# Qwiic_AHT20_Breakout.net
KiCad netlist of a schematic drawn in EAGLE
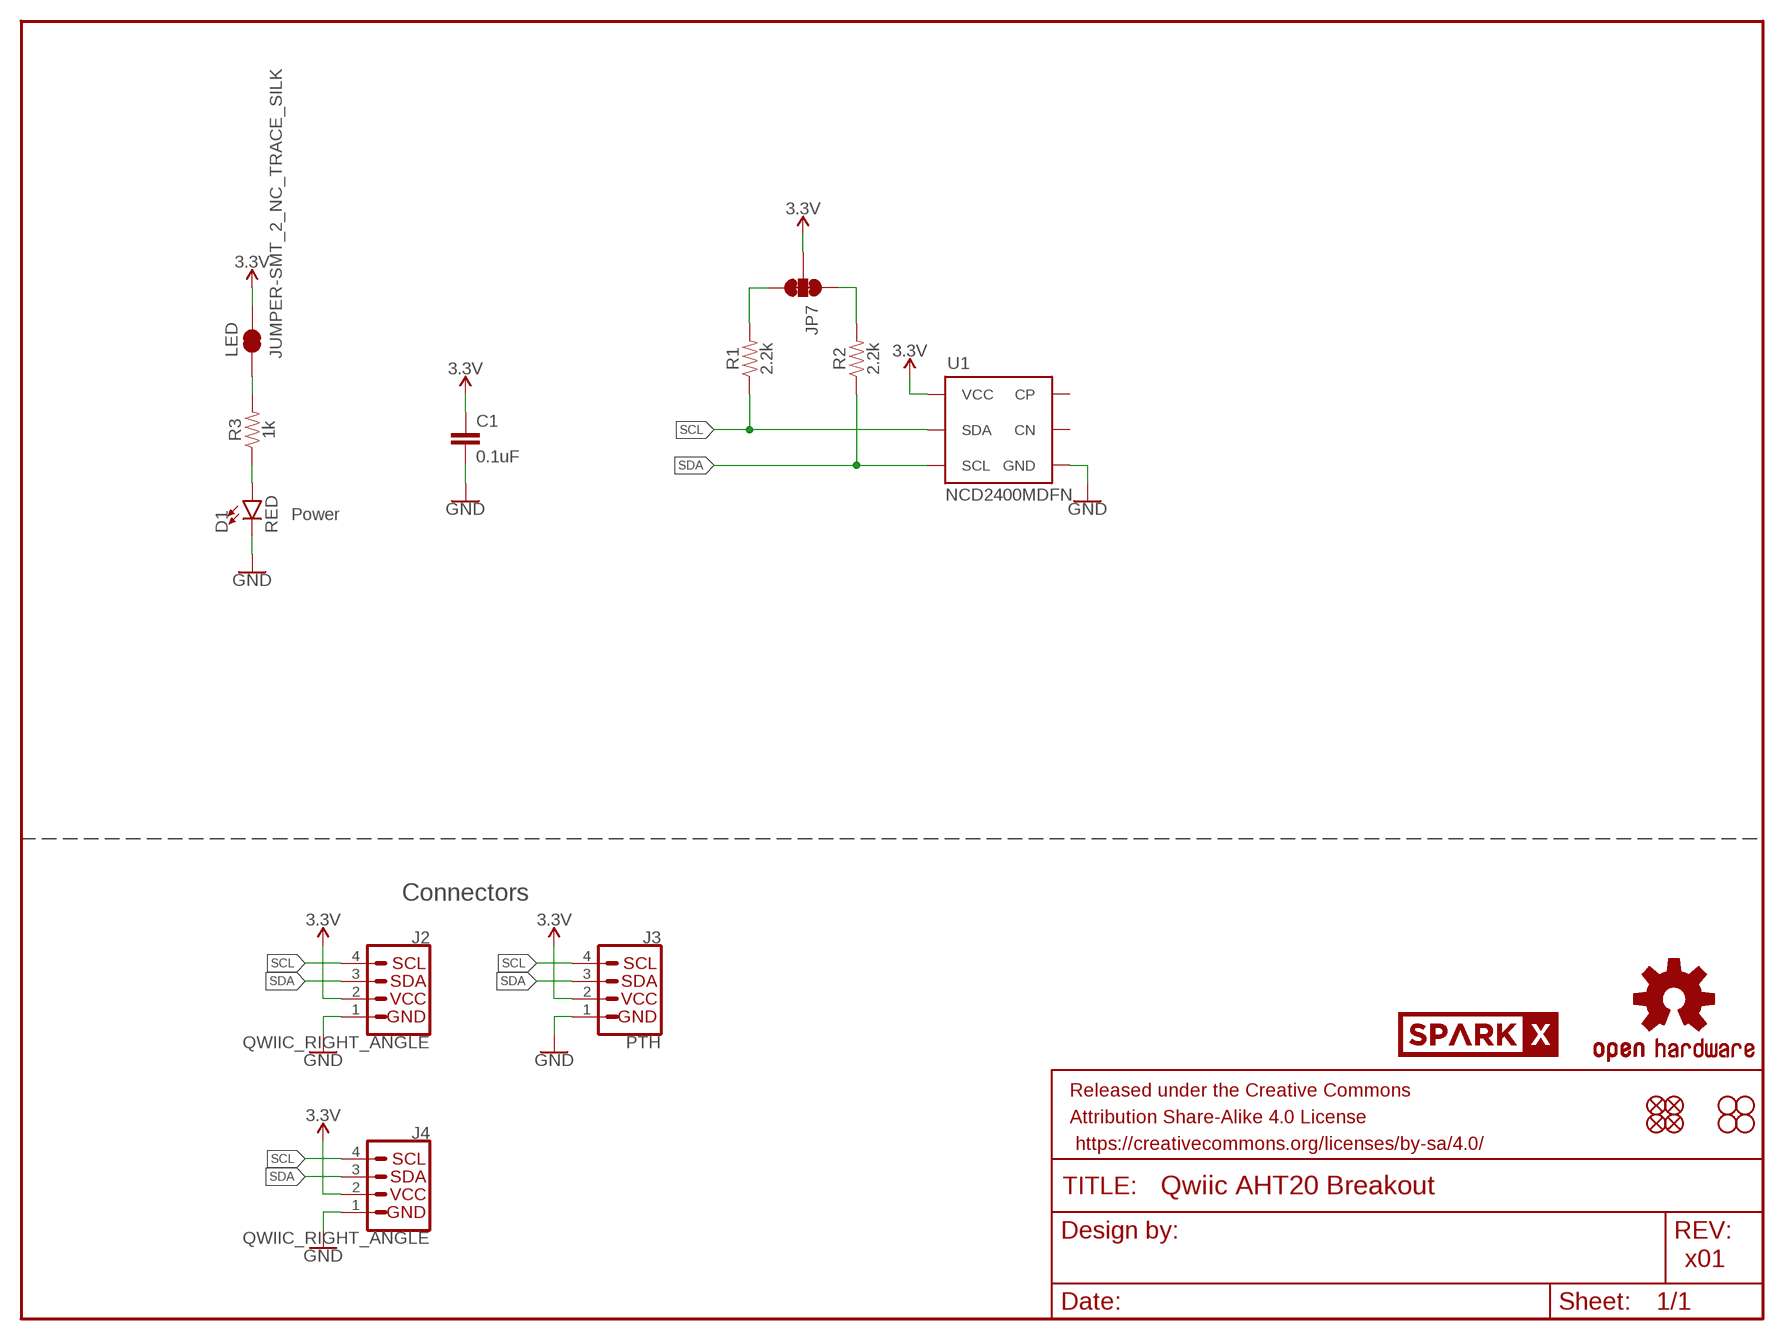
[diagram p0: schematic, sheet 1]

(export (version "E")
  (design (tool "Eeschema 10.0.6"))
  (components
    (comp (ref "C1")
      (value "0.1uF")
      (footprint "eagle-import:0603")
      (libsource (lib "eagle-import") (part "0.1UF-0603-25V-(+80/-20%)"))
    )
    (comp (ref "D1")
      (value "RED")
      (footprint "eagle-import:LED-0603")
      (libsource (lib "eagle-import") (part "LED-RED0603"))
    )
    (comp (ref "FRAME1")
      (value "FRAME-LETTER")
      (footprint "eagle-import:CREATIVE_COMMONS")
      (libsource (lib "eagle-import") (part "FRAME-LETTER"))
    )
    (comp (ref "J2")
      (value "QWIIC_RIGHT_ANGLE")
      (footprint "eagle-import:JST04_1MM_RA")
      (libsource (lib "eagle-import") (part "QWIIC_CONNECTORJS-1MM"))
    )
    (comp (ref "J3")
      (value "PTH")
      (footprint "eagle-import:1X04_NO_SILK")
      (libsource (lib "eagle-import") (part "I2C_STANDARD_NO_SILK"))
    )
    (comp (ref "J4")
      (value "QWIIC_RIGHT_ANGLE")
      (footprint "eagle-import:JST04_1MM_RA")
      (libsource (lib "eagle-import") (part "QWIIC_CONNECTORJS-1MM"))
    )
    (comp (ref "JP1")
      (value "FIDUCIAL1X2")
      (footprint "eagle-import:FIDUCIAL-1X2")
      (libsource (lib "eagle-import") (part "FIDUCIAL1X2"))
    )
    (comp (ref "JP2")
      (value "FIDUCIAL1X2")
      (footprint "eagle-import:FIDUCIAL-1X2")
      (libsource (lib "eagle-import") (part "FIDUCIAL1X2"))
    )
    (comp (ref "JP3")
      (value "STAND-OFF")
      (footprint "eagle-import:STAND-OFF")
      (libsource (lib "eagle-import") (part "STAND-OFF"))
    )
    (comp (ref "JP4")
      (value "STAND-OFF")
      (footprint "eagle-import:STAND-OFF")
      (libsource (lib "eagle-import") (part "STAND-OFF"))
    )
    (comp (ref "JP5")
      (value "FIDUCIAL1X2")
      (footprint "eagle-import:FIDUCIAL-1X2")
      (libsource (lib "eagle-import") (part "FIDUCIAL1X2"))
    )
    (comp (ref "JP6")
      (value "FIDUCIAL1X2")
      (footprint "eagle-import:FIDUCIAL-1X2")
      (libsource (lib "eagle-import") (part "FIDUCIAL1X2"))
    )
    (comp (ref "JP7")
      (value "JUMPER-SMT_3_2-NC_TRACE_SILK")
      (footprint "eagle-import:SMT-JUMPER_3_2-NC_TRACE_SILK")
      (libsource (lib "eagle-import") (part "JUMPER-SMT_3_2-NC_TRACE_SILK"))
    )
    (comp (ref "JP8")
      (value "STAND-OFF")
      (footprint "eagle-import:STAND-OFF")
      (libsource (lib "eagle-import") (part "STAND-OFF"))
    )
    (comp (ref "JP9")
      (value "STAND-OFF")
      (footprint "eagle-import:STAND-OFF")
      (libsource (lib "eagle-import") (part "STAND-OFF"))
    )
    (comp (ref "LED")
      (value "JUMPER-SMT_2_NC_TRACE_SILK")
      (footprint "eagle-import:SMT-JUMPER_2_NC_TRACE_SILK")
      (libsource (lib "eagle-import") (part "JUMPER-SMT_2_NC_TRACE_SILK"))
    )
    (comp (ref "LOGO1")
      (value "OSHW-LOGOMINI")
      (footprint "eagle-import:OSHW-LOGO-MINI")
      (libsource (lib "eagle-import") (part "OSHW-LOGOMINI"))
    )
    (comp (ref "R1")
      (value "2.2k")
      (footprint "eagle-import:0603")
      (libsource (lib "eagle-import") (part "2.2KOHM-0603-1/10W-1%"))
    )
    (comp (ref "R2")
      (value "2.2k")
      (footprint "eagle-import:0603")
      (libsource (lib "eagle-import") (part "2.2KOHM-0603-1/10W-1%"))
    )
    (comp (ref "R3")
      (value "1k")
      (footprint "eagle-import:0603")
      (libsource (lib "eagle-import") (part "1KOHM-0603-1/10W-1%"))
    )
    (comp (ref "U$1")
      (value "SPARKX-LOGO4")
      (footprint "eagle-import:SPARKX-MEDIUM")
      (libsource (lib "eagle-import") (part "SPARKX-LOGO4"))
    )
    (comp (ref "U$2")
      (value "SPARKX-LOGO4")
      (footprint "eagle-import:SPARKX-MEDIUM")
      (libsource (lib "eagle-import") (part "SPARKX-LOGO4"))
    )
    (comp (ref "U1")
      (value "NCD2400MDFN")
      (footprint "eagle-import:DFN6")
      (libsource (lib "eagle-import") (part "NCD2400MDFN"))
    )
  )
  (nets
    (net (code "1") (name "3.3V") (class "Default")
      (node (ref "C1") (pin "1") (pinfunction "1_1") (pintype "passive"))
      (node (ref "J2") (pin "2") (pinfunction "2_2") (pintype "power_in"))
      (node (ref "J3") (pin "2") (pinfunction "VCC_2") (pintype "power_in"))
      (node (ref "J4") (pin "2") (pinfunction "2_2") (pintype "power_in"))
      (node (ref "JP7") (pin "2") (pinfunction "2_2") (pintype "passive"))
      (node (ref "LED") (pin "2") (pinfunction "2_2") (pintype "passive"))
      (node (ref "U1") (pin "4") (pinfunction "VCC_4") (pintype "power_in"))
    )
    (net (code "2") (name "GND") (class "Default")
      (node (ref "C1") (pin "2") (pinfunction "2_2") (pintype "passive"))
      (node (ref "D1") (pin "C") (pinfunction "C_C") (pintype "passive"))
      (node (ref "J2") (pin "1") (pinfunction "1_1") (pintype "power_in"))
      (node (ref "J3") (pin "1") (pinfunction "GND_1") (pintype "power_in"))
      (node (ref "J4") (pin "1") (pinfunction "1_1") (pintype "power_in"))
      (node (ref "U1") (pin "5") (pinfunction "GND_5") (pintype "power_in"))
    )
    (net (code "3") (name "Net-(D1-PadA)") (class "Default")
      (node (ref "D1") (pin "A") (pinfunction "A_A") (pintype "passive"))
      (node (ref "R3") (pin "1") (pinfunction "1_1") (pintype "passive"))
    )
    (net (code "4") (name "Net-(JP7-Pad1)") (class "Default")
      (node (ref "JP7") (pin "1") (pinfunction "1_1") (pintype "passive"))
      (node (ref "R2") (pin "2") (pinfunction "2_2") (pintype "passive"))
    )
    (net (code "5") (name "Net-(JP7-Pad3)") (class "Default")
      (node (ref "JP7") (pin "3") (pinfunction "3_3") (pintype "passive"))
      (node (ref "R1") (pin "2") (pinfunction "2_2") (pintype "passive"))
    )
    (net (code "6") (name "Net-(LED-Pad1)") (class "Default")
      (node (ref "LED") (pin "1") (pinfunction "1_1") (pintype "passive"))
      (node (ref "R3") (pin "2") (pinfunction "2_2") (pintype "passive"))
    )
    (net (code "7") (name "SCL") (class "Default")
      (node (ref "J2") (pin "4") (pinfunction "4_4") (pintype "passive"))
      (node (ref "J3") (pin "4") (pinfunction "SCL_4") (pintype "passive"))
      (node (ref "J4") (pin "4") (pinfunction "4_4") (pintype "passive"))
      (node (ref "R1") (pin "1") (pinfunction "1_1") (pintype "passive"))
      (node (ref "U1") (pin "1") (pinfunction "SDA_1") (pintype "bidirectional"))
    )
    (net (code "8") (name "SDA") (class "Default")
      (node (ref "J2") (pin "3") (pinfunction "3_3") (pintype "passive"))
      (node (ref "J3") (pin "3") (pinfunction "SDA_3") (pintype "passive"))
      (node (ref "J4") (pin "3") (pinfunction "3_3") (pintype "passive"))
      (node (ref "R2") (pin "1") (pinfunction "1_1") (pintype "passive"))
      (node (ref "U1") (pin "6") (pinfunction "SCL_6") (pintype "bidirectional"))
    )
    (net (code "9") (name "unconnected-(U1-CN-Pad3)") (class "Default")
      (node (ref "U1") (pin "3") (pinfunction "CN_3") (pintype "output"))
    )
    (net (code "10") (name "unconnected-(U1-CP-Pad2)") (class "Default")
      (node (ref "U1") (pin "2") (pinfunction "CP_2") (pintype "output"))
    )
  )
)
